# ACS712.net
KiCad netlist of a schematic drawn in Altium Designer
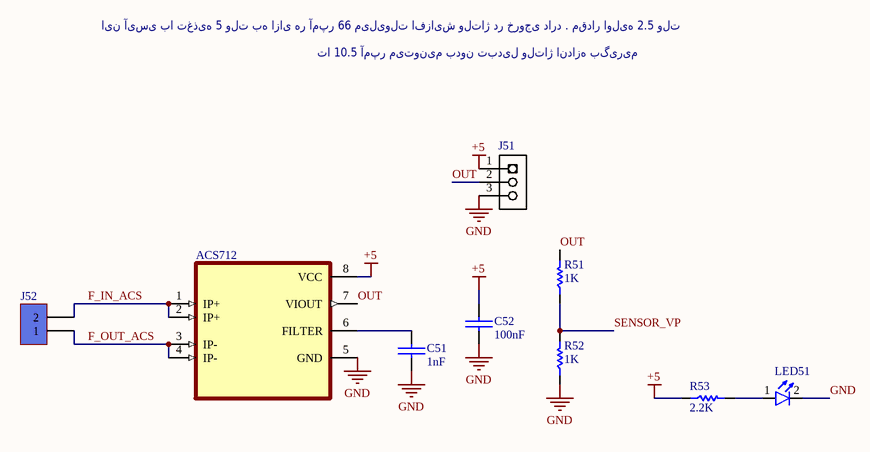
[diagram p0: ACS712.SchDoc]

(export (version "E")
  (design (tool "Eeschema 10.0.6"))
  (components
    (comp (ref "ACS712")
      (value "ACS712ELCTR30AT")
      (footprint "SOIC127P600X175-8N")
      (description "Current Sensor 30A 1 Channel Hall Effect, Open Loop Bidirectional 8-SOIC _0.154, 3.90mm Width_")
      (fields (field (name "MF") "Allegro MicroSystems LLC"))
      (libsource (lib "ACS712ELCTR30AT") (part "ACS712ELCTR30AT"))
    )
    (comp (ref "C51")
      (value "1nF")
      (footprint "SMD_CAP_0805")
      (description "Bipolar Capacitor")
      (fields (field (name "VOLTAGE") "100V") (field (name "DESIGNER") "Saeid Jorablo"))
      (libsource (lib "DDEms") (part "Cap-Bipolar"))
    )
    (comp (ref "C52")
      (value "100nF")
      (footprint "SMD_CAP_0805")
      (description "Bipolar Capacitor")
      (fields (field (name "VOLTAGE") "100V") (field (name "DESIGNER") "Saeid Jorablo"))
      (libsource (lib "DDEms") (part "Cap-Bipolar"))
    )
    (comp (ref "J51")
      (value "HEADER-1X3")
      (footprint "HEADER-1X3")
      (libsource (lib "General_05") (part "HEADER-1X3"))
    )
    (comp (ref "J52") (value "J1") (footprint "KF301 2PIN") (libsource (lib "DDEms") (part "Terminal_2pin")))
    (comp (ref "LED51")
      (value "Red")
      (footprint "LED_SMD_0805")
      (description "LED")
      (fields (field (name "DESIGNER") "Saeid Jorablo"))
      (libsource (lib "DDEms") (part "LED"))
    )
    (comp (ref "R51")
      (value "1K")
      (footprint "SMD_RES_0805")
      (description "Resistor")
      (fields (field (name "TOLERANCE") "5%") (field (name "POWER") "1/8 W"))
      (libsource (lib "DDEms") (part "Resistor"))
    )
    (comp (ref "R52")
      (value "1K")
      (footprint "SMD_RES_0805")
      (description "Resistor")
      (fields (field (name "TOLERANCE") "5%") (field (name "POWER") "1/8 W"))
      (libsource (lib "DDEms") (part "Resistor"))
    )
    (comp (ref "R53")
      (value "2.2K")
      (footprint "SMD_RES_0805")
      (description "Resistor")
      (fields (field (name "TOLERANCE") "5%") (field (name "POWER") "1/8 W"))
      (libsource (lib "DDEms") (part "Resistor"))
    )
  )
  (nets
    (net (code "1") (name "+5") (class "Default")
      (node (ref "ACS712") (pin "8") (pinfunction "VCC_8") (pintype "power_in"))
      (node (ref "C52") (pin "1") (pinfunction "+_1") (pintype "passive"))
      (node (ref "J51") (pin "1") (pintype "passive"))
      (node (ref "R53") (pin "1") (pinfunction "1_1") (pintype "passive"))
    )
    (net (code "2") (name "/F_IN_ACS") (class "Default")
      (node (ref "ACS712") (pin "1") (pinfunction "IP+_1") (pintype "input"))
      (node (ref "ACS712") (pin "2") (pinfunction "IP+_2") (pintype "input"))
      (node (ref "J52") (pin "2") (pinfunction "2_2") (pintype "passive"))
    )
    (net (code "3") (name "/F_OUT_ACS") (class "Default")
      (node (ref "ACS712") (pin "3") (pinfunction "IP-_3") (pintype "input"))
      (node (ref "ACS712") (pin "4") (pinfunction "IP-_4") (pintype "input"))
      (node (ref "J52") (pin "1") (pinfunction "1_1") (pintype "passive"))
    )
    (net (code "4") (name "/OUT") (class "Default")
      (node (ref "ACS712") (pin "7") (pinfunction "VIOUT_7") (pintype "output"))
      (node (ref "J51") (pin "2") (pintype "passive"))
      (node (ref "R51") (pin "2") (pinfunction "2_2") (pintype "passive"))
    )
    (net (code "5") (name "/SENSOR_VP") (class "Default")
      (node (ref "R51") (pin "1") (pinfunction "1_1") (pintype "passive"))
      (node (ref "R52") (pin "2") (pinfunction "2_2") (pintype "passive"))
    )
    (net (code "6") (name "GND") (class "Default")
      (node (ref "ACS712") (pin "5") (pinfunction "GND_5") (pintype "power_in"))
      (node (ref "C51") (pin "2") (pinfunction "-_2") (pintype "passive"))
      (node (ref "C52") (pin "2") (pinfunction "-_2") (pintype "passive"))
      (node (ref "J51") (pin "3") (pintype "passive"))
      (node (ref "LED51") (pin "2") (pinfunction "K_2") (pintype "passive"))
      (node (ref "R52") (pin "1") (pinfunction "1_1") (pintype "passive"))
    )
    (net (code "7") (name "Net-(ACS712-FILTER)") (class "Default")
      (node (ref "ACS712") (pin "6") (pinfunction "FILTER_6") (pintype "passive"))
      (node (ref "C51") (pin "1") (pinfunction "+_1") (pintype "passive"))
    )
    (net (code "8") (name "Net-(LED51-A)") (class "Default")
      (node (ref "LED51") (pin "1") (pinfunction "A_1") (pintype "passive"))
      (node (ref "R53") (pin "2") (pinfunction "2_2") (pintype "passive"))
    )
  )
)
